# Sheet1.net
KiCad netlist of a schematic drawn in Altium Designer
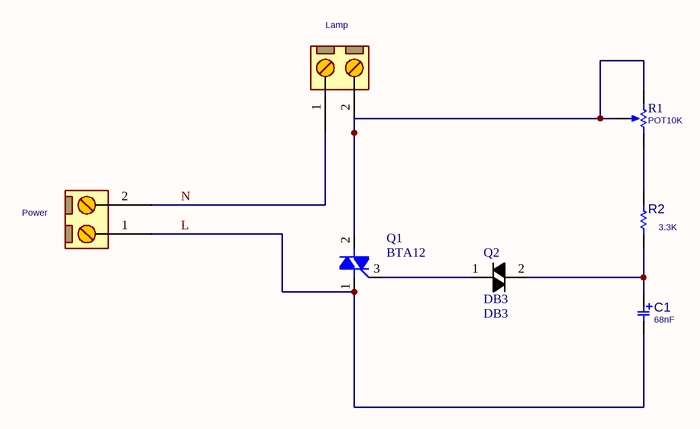
[diagram p0: Sheet1.SchDoc]

(export (version "E")
  (design (tool "Eeschema 10.0.6"))
  (components
    (comp (ref "C1")
      (value "68nF")
      (footprint "C_FLM_7X5H11")
      (description "CAP, THD, FILM,")
      (fields (field (name "MANF_P#") "MANF_PART#") (field (name "MANF") "MANF"))
      (libsource (lib "passive_thd") (part "CAP_THD_FLM"))
    )
    (comp (ref "Lamp")
      (value "CONN_TB2")
      (footprint "MSTB_2")
      (description "CONN, PHOENIX MSTB, 5-G, 5.08mm pitch")
      (libsource (lib "conn_terminalB") (part "CONN_MSTB_2"))
    )
    (comp (ref "Power")
      (value "CONN_TB2")
      (footprint "MSTB_2")
      (description "CONN, PHOENIX MSTB, 5-G, 5.08mm pitch")
      (libsource (lib "") (part "CONN_MSTB_2_1"))
    )
    (comp (ref "Q1")
      (value "BTA12")
      (footprint "TO220_3")
      (description "Triac, 600V, 12A, TO-220")
      (fields (field (name "MANF_P#") "BTA12-600BW, BTA12-600CW, BTA12-600TW") (field (name "MANF") "ST"))
      (libsource (lib "triac_diac") (part "TRIAC_BTA12-600_TO220"))
    )
    (comp (ref "Q2")
      (value "DB3")
      (footprint "D_AX03_DO35")
      (description "Diac, 32VBO, DO-35")
      (fields (field (name "MANF") "ST") (field (name "ALTIUM_VALUE") "DB3"))
      (libsource (lib "triac_diac") (part "DIAC_DB3_DO35"))
    )
    (comp (ref "R1")
      (value "POT10K")
      (footprint "VOL_R")
      (description "RESISTOR, THD, Potentiometer Volume")
      (libsource (lib "resistor_pot_trimmer") (part "RES_THD_POT_VOLUME"))
    )
    (comp (ref "R2")
      (value "3.3K")
      (footprint "R025W_AX04")
      (description "RESISTOR, THD")
      (fields (field (name "MANF_P#") "RK73H1ETTP4701F") (field (name "MANF") "KOA SPEER"))
      (libsource (lib "passive_thd") (part "RES_THD"))
    )
  )
  (nets
    (net (code "1") (name "/L") (class "Default")
      (node (ref "C1") (pin "2") (pinfunction "2_2") (pintype "passive"))
      (node (ref "Power") (pin "1") (pinfunction "1_1") (pintype "passive"))
      (node (ref "Q1") (pin "1") (pinfunction "T1_1") (pintype "passive"))
    )
    (net (code "2") (name "/N") (class "Default")
      (node (ref "Lamp") (pin "1") (pinfunction "1_1") (pintype "passive"))
      (node (ref "Power") (pin "2") (pinfunction "2_2") (pintype "passive"))
    )
    (net (code "3") (name "Net-(Q1-G)") (class "Default")
      (node (ref "Q1") (pin "3") (pinfunction "G_3") (pintype "passive"))
      (node (ref "Q2") (pin "1") (pinfunction "A1_1") (pintype "passive"))
    )
    (net (code "4") (name "Net-(Q1-T2)") (class "Default")
      (node (ref "Lamp") (pin "2") (pinfunction "2_2") (pintype "passive"))
      (node (ref "Q1") (pin "2") (pinfunction "T2_2") (pintype "passive"))
      (node (ref "R1") (pin "1") (pinfunction "TOP_1") (pintype "passive"))
      (node (ref "R1") (pin "2") (pinfunction "TAP_2") (pintype "passive"))
    )
    (net (code "5") (name "Net-(Q2-A2)") (class "Default")
      (node (ref "C1") (pin "1") (pinfunction "1_1") (pintype "passive"))
      (node (ref "Q2") (pin "2") (pinfunction "A2_2") (pintype "passive"))
      (node (ref "R2") (pin "1") (pinfunction "1_1") (pintype "passive"))
    )
    (net (code "6") (name "Net-(R1-BOT)") (class "Default")
      (node (ref "R1") (pin "3") (pinfunction "BOT_3") (pintype "passive"))
      (node (ref "R2") (pin "2") (pinfunction "2_2") (pintype "passive"))
    )
  )
)
